# optoEncoder.net
KiCad netlist of a schematic drawn in Altium Designer
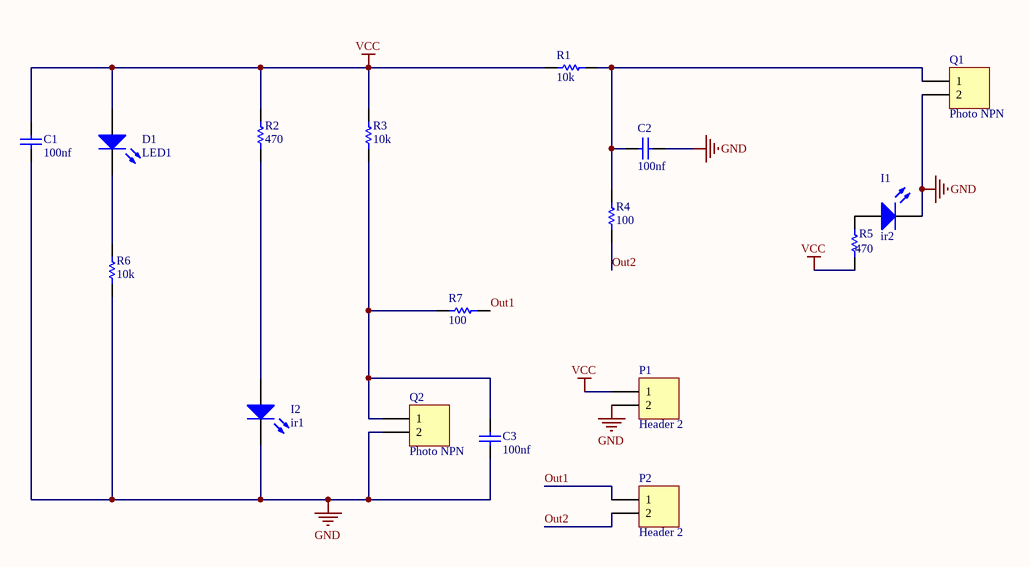
[diagram p0: optoEncoder.SchDoc]

(export (version "E")
  (design (tool "Eeschema 10.0.6"))
  (components
    (comp (ref "C1")
      (value "100nf")
      (footprint "6-0805_M")
      (description "Capacitor")
      (fields (field (name "Comment") "Cap") (field (name "PUBLISHER") "Altium Limited"))
      (libsource (lib "Miscellaneous Devices") (part "Cap"))
    )
    (comp (ref "C2")
      (value "100nf")
      (footprint "6-0805_M")
      (description "Capacitor")
      (fields (field (name "Comment") "Cap") (field (name "PUBLISHER") "Altium Limited"))
      (libsource (lib "Miscellaneous Devices") (part "Cap"))
    )
    (comp (ref "C3")
      (value "100nf")
      (footprint "6-0805_M")
      (description "Capacitor")
      (fields (field (name "Comment") "Cap") (field (name "PUBLISHER") "Altium Limited"))
      (libsource (lib "Miscellaneous Devices") (part "Cap"))
    )
    (comp (ref "D1")
      (value "LED1")
      (footprint "6-0805_M")
      (description "Typical RED, GREEN, YELLOW, AMBER GaAs LED")
      (fields (field (name "PUBLISHER") "Altium Limited"))
      (libsource (lib "Miscellaneous Devices") (part "LED2"))
    )
    (comp (ref "I1")
      (value "ir2")
      (footprint "hdr1x2")
      (description "Typical INFRARED GaAs LED")
      (fields (field (name "PUBLISHER") "Altium Limited"))
      (libsource (lib "Miscellaneous Devices") (part "LED0"))
    )
    (comp (ref "I2")
      (value "ir1")
      (footprint "HDR1X2")
      (description "Typical INFRARED GaAs LED")
      (fields (field (name "PUBLISHER") "Altium Limited"))
      (libsource (lib "Miscellaneous Devices") (part "LED0"))
    )
    (comp (ref "P1")
      (value "Header 2")
      (footprint "HDR1X2")
      (description "Header, 2-Pin")
      (fields (field (name "PUBLISHER") "Altium Limited"))
      (libsource (lib "Miscellaneous Connectors") (part "Header 2"))
    )
    (comp (ref "P2")
      (value "Header 2")
      (footprint "HDR1X2")
      (description "Header, 2-Pin")
      (fields (field (name "PUBLISHER") "Altium Limited"))
      (libsource (lib "Miscellaneous Connectors") (part "Header 2"))
    )
    (comp (ref "Q1")
      (value "Photo NPN")
      (footprint "HDR1X2")
      (description "Header, 2-Pin")
      (fields (field (name "PUBLISHER") "Altium Limited"))
      (libsource (lib "Miscellaneous Connectors") (part "Header 2"))
    )
    (comp (ref "Q2")
      (value "Photo NPN")
      (footprint "HDR1X2")
      (description "Header, 2-Pin")
      (fields (field (name "PUBLISHER") "Altium Limited"))
      (libsource (lib "Miscellaneous Connectors") (part "Header 2"))
    )
    (comp (ref "R1")
      (value "10k")
      (footprint "6-0805_M")
      (description "Resistor")
      (fields (field (name "Comment") "Res1") (field (name "PUBLISHER") "Altium Limited"))
      (libsource (lib "Miscellaneous Devices") (part "Res1"))
    )
    (comp (ref "R2")
      (value "470")
      (footprint "6-0805_M")
      (description "Resistor")
      (fields (field (name "Comment") "Res1") (field (name "PUBLISHER") "Altium Limited"))
      (libsource (lib "Miscellaneous Devices") (part "Res1"))
    )
    (comp (ref "R3")
      (value "10k")
      (footprint "6-0805_M")
      (description "Resistor")
      (fields (field (name "Comment") "Res1") (field (name "PUBLISHER") "Altium Limited"))
      (libsource (lib "Miscellaneous Devices") (part "Res1"))
    )
    (comp (ref "R4")
      (value "100")
      (footprint "6-0805_M")
      (description "Resistor")
      (fields (field (name "Comment") "Res1") (field (name "PUBLISHER") "Altium Limited"))
      (libsource (lib "Miscellaneous Devices") (part "Res1"))
    )
    (comp (ref "R5")
      (value "470")
      (footprint "6-0805_M")
      (description "Resistor")
      (fields (field (name "Comment") "Res1") (field (name "PUBLISHER") "Altium Limited"))
      (libsource (lib "Miscellaneous Devices") (part "Res1"))
    )
    (comp (ref "R6")
      (value "10k")
      (footprint "6-0805_M")
      (description "Resistor")
      (fields (field (name "Comment") "Res1") (field (name "PUBLISHER") "Altium Limited"))
      (libsource (lib "Miscellaneous Devices") (part "Res1"))
    )
    (comp (ref "R7")
      (value "100")
      (footprint "6-0805_M")
      (description "Resistor")
      (fields (field (name "Comment") "Res1") (field (name "PUBLISHER") "Altium Limited"))
      (libsource (lib "Miscellaneous Devices") (part "Res1"))
    )
  )
  (nets
    (net (code "1") (name "/Out1") (class "Default")
      (node (ref "P2") (pin "1") (pinfunction "1_1") (pintype "passive"))
      (node (ref "R7") (pin "2") (pinfunction "2_2") (pintype "passive"))
    )
    (net (code "2") (name "/Out2") (class "Default")
      (node (ref "P2") (pin "2") (pinfunction "2_2") (pintype "passive"))
      (node (ref "R4") (pin "1") (pinfunction "1_1") (pintype "passive"))
    )
    (net (code "3") (name "GND") (class "Default")
      (node (ref "C1") (pin "2") (pinfunction "2_2") (pintype "passive"))
      (node (ref "C2") (pin "1") (pinfunction "1_1") (pintype "passive"))
      (node (ref "C3") (pin "2") (pinfunction "2_2") (pintype "passive"))
      (node (ref "I1") (pin "2") (pinfunction "K_2") (pintype "passive"))
      (node (ref "I2") (pin "2") (pinfunction "K_2") (pintype "passive"))
      (node (ref "P1") (pin "2") (pinfunction "2_2") (pintype "passive"))
      (node (ref "Q1") (pin "2") (pinfunction "2_2") (pintype "passive"))
      (node (ref "Q2") (pin "2") (pinfunction "2_2") (pintype "passive"))
      (node (ref "R6") (pin "2") (pinfunction "2_2") (pintype "passive"))
    )
    (net (code "4") (name "Net-(C2-Pad2)") (class "Default")
      (node (ref "C2") (pin "2") (pinfunction "2_2") (pintype "passive"))
      (node (ref "Q1") (pin "1") (pinfunction "1_1") (pintype "passive"))
      (node (ref "R1") (pin "2") (pinfunction "2_2") (pintype "passive"))
      (node (ref "R4") (pin "2") (pinfunction "2_2") (pintype "passive"))
    )
    (net (code "5") (name "Net-(C3-Pad1)") (class "Default")
      (node (ref "C3") (pin "1") (pinfunction "1_1") (pintype "passive"))
      (node (ref "Q2") (pin "1") (pinfunction "1_1") (pintype "passive"))
      (node (ref "R3") (pin "2") (pinfunction "2_2") (pintype "passive"))
      (node (ref "R7") (pin "1") (pinfunction "1_1") (pintype "passive"))
    )
    (net (code "6") (name "Net-(D1-K)") (class "Default")
      (node (ref "D1") (pin "2") (pinfunction "K_2") (pintype "passive"))
      (node (ref "R6") (pin "1") (pinfunction "1_1") (pintype "passive"))
    )
    (net (code "7") (name "Net-(I1-A)") (class "Default")
      (node (ref "I1") (pin "1") (pinfunction "A_1") (pintype "passive"))
      (node (ref "R5") (pin "2") (pinfunction "2_2") (pintype "passive"))
    )
    (net (code "8") (name "Net-(I2-A)") (class "Default")
      (node (ref "I2") (pin "1") (pinfunction "A_1") (pintype "passive"))
      (node (ref "R2") (pin "1") (pinfunction "1_1") (pintype "passive"))
    )
    (net (code "9") (name "VCC") (class "Default")
      (node (ref "C1") (pin "1") (pinfunction "1_1") (pintype "passive"))
      (node (ref "D1") (pin "1") (pinfunction "A_1") (pintype "passive"))
      (node (ref "P1") (pin "1") (pinfunction "1_1") (pintype "passive"))
      (node (ref "R1") (pin "1") (pinfunction "1_1") (pintype "passive"))
      (node (ref "R2") (pin "2") (pinfunction "2_2") (pintype "passive"))
      (node (ref "R3") (pin "1") (pinfunction "1_1") (pintype "passive"))
      (node (ref "R5") (pin "1") (pinfunction "1_1") (pintype "passive"))
    )
  )
)
